# moth_v3_54mm_breakout.net
KiCad netlist of a schematic drawn in EAGLE
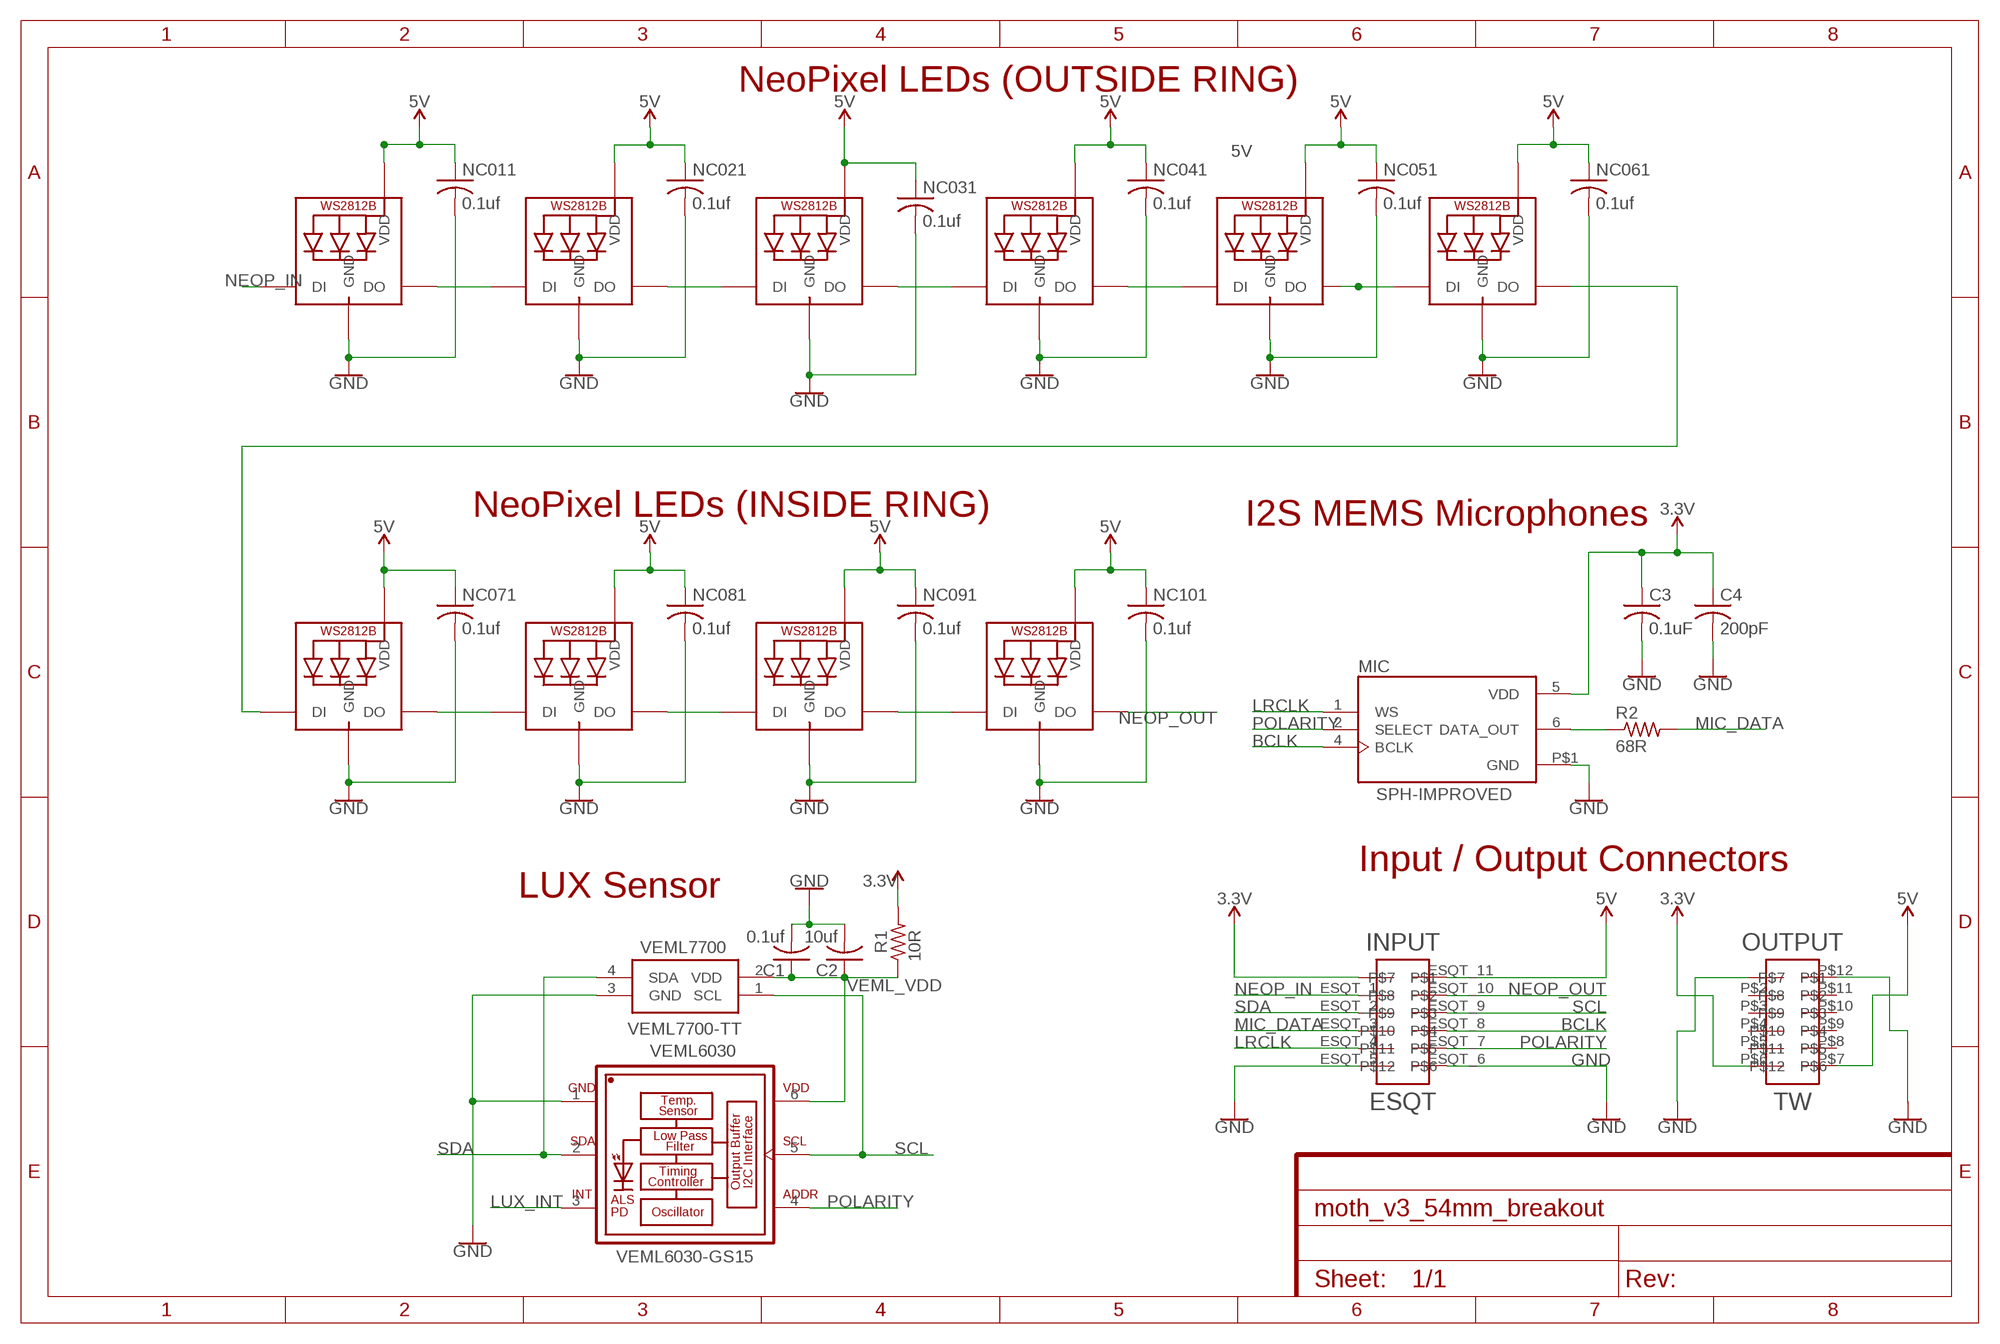
[diagram p0: schematic, sheet 1]

(export (version "E")
  (design (tool "Eeschema 10.0.6"))
  (components
    (comp (ref "C1")
      (value "0.1uf")
      (footprint "eagle-import:C0805")
      (libsource (lib "eagle-import") (part "C-USC0805"))
    )
    (comp (ref "C2")
      (value "10uf")
      (footprint "eagle-import:C0805")
      (libsource (lib "eagle-import") (part "C-USC0805"))
    )
    (comp (ref "C3")
      (value "0.1uF")
      (footprint "eagle-import:C0805")
      (libsource (lib "eagle-import") (part "C-USC0805"))
    )
    (comp (ref "C4")
      (value "200pF")
      (footprint "eagle-import:C0805")
      (libsource (lib "eagle-import") (part "C-USC0805"))
    )
    (comp (ref "INPUT")
      (value "ESQT")
      (footprint "eagle-import:SAMTEC_ESQT_2X6_THROUGH_HOLE")
      (libsource (lib "eagle-import") (part "SAMTEC_ESQT_2X6_THROUGH_HOLE"))
    )
    (comp (ref "MIC")
      (value "SPH-IMPROVED")
      (footprint "eagle-import:MIC_SPH0645LM4H-B_LARGER_RING")
      (libsource (lib "eagle-import") (part "SPH-IMPROVED"))
    )
    (comp (ref "NC011")
      (value "0.1uf")
      (footprint "eagle-import:C0805K")
      (libsource (lib "eagle-import") (part "C-USC0805K"))
    )
    (comp (ref "NC021")
      (value "0.1uf")
      (footprint "eagle-import:C0805K")
      (libsource (lib "eagle-import") (part "C-USC0805K"))
    )
    (comp (ref "NC031")
      (value "0.1uf")
      (footprint "eagle-import:C0805K")
      (libsource (lib "eagle-import") (part "C-USC0805K"))
    )
    (comp (ref "NC041")
      (value "0.1uf")
      (footprint "eagle-import:C0805K")
      (libsource (lib "eagle-import") (part "C-USC0805K"))
    )
    (comp (ref "NC051")
      (value "0.1uf")
      (footprint "eagle-import:C0805K")
      (libsource (lib "eagle-import") (part "C-USC0805K"))
    )
    (comp (ref "NC061")
      (value "0.1uf")
      (footprint "eagle-import:C0805K")
      (libsource (lib "eagle-import") (part "C-USC0805K"))
    )
    (comp (ref "NC071")
      (value "0.1uf")
      (footprint "eagle-import:C0805K")
      (libsource (lib "eagle-import") (part "C-USC0805K"))
    )
    (comp (ref "NC081")
      (value "0.1uf")
      (footprint "eagle-import:C0805K")
      (libsource (lib "eagle-import") (part "C-USC0805K"))
    )
    (comp (ref "NC091")
      (value "0.1uf")
      (footprint "eagle-import:C0805K")
      (libsource (lib "eagle-import") (part "C-USC0805K"))
    )
    (comp (ref "NC101")
      (value "0.1uf")
      (footprint "eagle-import:C0805K")
      (libsource (lib "eagle-import") (part "C-USC0805K"))
    )
    (comp (ref "NEO1")
      (value "WS2812B5050")
      (footprint "eagle-import:WS2812B")
      (libsource (lib "eagle-import") (part "WS2812B5050"))
    )
    (comp (ref "NEO2")
      (value "WS2812B5050")
      (footprint "eagle-import:WS2812B")
      (libsource (lib "eagle-import") (part "WS2812B5050"))
    )
    (comp (ref "NEO3")
      (value "WS2812B5050")
      (footprint "eagle-import:WS2812B")
      (libsource (lib "eagle-import") (part "WS2812B5050"))
    )
    (comp (ref "NEO4")
      (value "WS2812B5050")
      (footprint "eagle-import:WS2812B")
      (libsource (lib "eagle-import") (part "WS2812B5050"))
    )
    (comp (ref "NEO5")
      (value "WS2812B5050")
      (footprint "eagle-import:WS2812B")
      (libsource (lib "eagle-import") (part "WS2812B5050"))
    )
    (comp (ref "NEO6")
      (value "WS2812B5050")
      (footprint "eagle-import:WS2812B")
      (libsource (lib "eagle-import") (part "WS2812B5050"))
    )
    (comp (ref "NEO07")
      (value "WS2812B5050")
      (footprint "eagle-import:WS2812B")
      (libsource (lib "eagle-import") (part "WS2812B5050"))
    )
    (comp (ref "NEO08")
      (value "WS2812B5050")
      (footprint "eagle-import:WS2812B")
      (libsource (lib "eagle-import") (part "WS2812B5050"))
    )
    (comp (ref "NEO9")
      (value "WS2812B5050")
      (footprint "eagle-import:WS2812B")
      (libsource (lib "eagle-import") (part "WS2812B5050"))
    )
    (comp (ref "NEO10")
      (value "WS2812B5050")
      (footprint "eagle-import:WS2812B")
      (libsource (lib "eagle-import") (part "WS2812B5050"))
    )
    (comp (ref "OUTPUT")
      (value "TW")
      (footprint "eagle-import:SAMTEC_TW_2X6")
      (libsource (lib "eagle-import") (part "SAMTEC_TW_2X6_WITH_STABLE"))
    )
    (comp (ref "R1")
      (value "10R")
      (footprint "eagle-import:R0805")
      (libsource (lib "eagle-import") (part "audio amplifier example_970892_R-US_R0805"))
    )
    (comp (ref "R2")
      (value "68R")
      (footprint "eagle-import:M0805")
      (libsource (lib "eagle-import") (part "R-US_M0805"))
    )
    (comp (ref "VEML6030")
      (value "VEML6030-GS15")
      (footprint "eagle-import:VISHAY_VEML6030_2X2X0.87")
      (fields (field (name "MF") "Vishay Semiconductor"))
      (libsource (lib "eagle-import") (part "VEML6030-GS15"))
    )
    (comp (ref "VEML7700")
      (value "VEML7700-TT")
      (footprint "eagle-import:VEML7700")
      (fields (field (name "MOUSER_PART_NUMBER") "78-VEML7700-TT") (field (name "RS_PART_NUMBER") "1226791P"))
      (libsource (lib "eagle-import") (part "VEML7700-TT"))
    )
  )
  (nets
    (net (code "1") (name "/BCLK") (class "Default")
      (node (ref "INPUT") (pin "ESQT_8") (pinfunction "P$10_ESQT_8") (pintype "bidirectional"))
      (node (ref "MIC") (pin "4") (pinfunction "BCLK_4") (pintype "input"))
    )
    (net (code "2") (name "/LRCLK") (class "Default")
      (node (ref "INPUT") (pin "ESQT_4") (pinfunction "P$5_ESQT_4") (pintype "bidirectional"))
      (node (ref "MIC") (pin "1") (pinfunction "WS_1") (pintype "input"))
    )
    (net (code "3") (name "/LUX_INT") (class "Default")
      (node (ref "VEML6030") (pin "3") (pinfunction "INT_3") (pintype "output"))
    )
    (net (code "4") (name "/MIC_DATA") (class "Default")
      (node (ref "INPUT") (pin "ESQT_3") (pinfunction "P$4_ESQT_3") (pintype "bidirectional"))
      (node (ref "R2") (pin "2") (pinfunction "2_2") (pintype "passive"))
    )
    (net (code "5") (name "/NEOP_IN") (class "Default")
      (node (ref "INPUT") (pin "ESQT_1") (pinfunction "P$2_ESQT_1") (pintype "bidirectional"))
      (node (ref "NEO1") (pin "4-DIN") (pinfunction "DI_4-DIN") (pintype "input"))
    )
    (net (code "6") (name "/NEOP_OUT") (class "Default")
      (node (ref "INPUT") (pin "ESQT_10") (pinfunction "P$8_ESQT_10") (pintype "bidirectional"))
      (node (ref "NEO10") (pin "2-DOUT") (pinfunction "DO_2-DOUT") (pintype "output"))
    )
    (net (code "7") (name "/POLARITY") (class "Default")
      (node (ref "INPUT") (pin "ESQT_7") (pinfunction "P$11_ESQT_7") (pintype "bidirectional"))
      (node (ref "MIC") (pin "2") (pinfunction "SELECT_2") (pintype "input"))
      (node (ref "VEML6030") (pin "4") (pinfunction "ADDR_4") (pintype "bidirectional"))
    )
    (net (code "8") (name "/SCL") (class "Default")
      (node (ref "INPUT") (pin "ESQT_9") (pinfunction "P$9_ESQT_9") (pintype "bidirectional"))
      (node (ref "VEML6030") (pin "5") (pinfunction "SCL_5") (pintype "input"))
      (node (ref "VEML7700") (pin "1") (pinfunction "SCL_1") (pintype "bidirectional"))
    )
    (net (code "9") (name "/SDA") (class "Default")
      (node (ref "INPUT") (pin "ESQT_2") (pinfunction "P$3_ESQT_2") (pintype "bidirectional"))
      (node (ref "VEML6030") (pin "2") (pinfunction "SDA_2") (pintype "bidirectional"))
      (node (ref "VEML7700") (pin "4") (pinfunction "SDA_4") (pintype "bidirectional"))
    )
    (net (code "10") (name "/VEML_VDD") (class "Default")
      (node (ref "C1") (pin "1") (pinfunction "1_1") (pintype "passive"))
      (node (ref "C2") (pin "1") (pinfunction "1_1") (pintype "passive"))
      (node (ref "R1") (pin "1") (pinfunction "1_1") (pintype "passive"))
      (node (ref "VEML6030") (pin "6") (pinfunction "VDD_6") (pintype "power_in"))
      (node (ref "VEML7700") (pin "2") (pinfunction "VDD_2") (pintype "bidirectional"))
    )
    (net (code "11") (name "3.3V") (class "Default")
      (node (ref "C3") (pin "1") (pinfunction "1_1") (pintype "passive"))
      (node (ref "C4") (pin "1") (pinfunction "1_1") (pintype "passive"))
      (node (ref "INPUT") (pin "ESQT_0") (pinfunction "P$1_ESQT_0") (pintype "bidirectional"))
      (node (ref "MIC") (pin "5") (pinfunction "VDD_5") (pintype "power_in"))
      (node (ref "OUTPUT") (pin "P$6") (pinfunction "P$6_P$6") (pintype "bidirectional"))
      (node (ref "R1") (pin "2") (pinfunction "2_2") (pintype "passive"))
    )
    (net (code "12") (name "5V") (class "Default")
      (node (ref "INPUT") (pin "ESQT_11") (pinfunction "P$7_ESQT_11") (pintype "bidirectional"))
      (node (ref "NC011") (pin "1") (pinfunction "1_1") (pintype "passive"))
      (node (ref "NC021") (pin "1") (pinfunction "1_1") (pintype "passive"))
      (node (ref "NC031") (pin "1") (pinfunction "1_1") (pintype "passive"))
      (node (ref "NC041") (pin "1") (pinfunction "1_1") (pintype "passive"))
      (node (ref "NC051") (pin "1") (pinfunction "1_1") (pintype "passive"))
      (node (ref "NC061") (pin "1") (pinfunction "1_1") (pintype "passive"))
      (node (ref "NC071") (pin "1") (pinfunction "1_1") (pintype "passive"))
      (node (ref "NC081") (pin "1") (pinfunction "1_1") (pintype "passive"))
      (node (ref "NC091") (pin "1") (pinfunction "1_1") (pintype "passive"))
      (node (ref "NC101") (pin "1") (pinfunction "1_1") (pintype "passive"))
      (node (ref "NEO07") (pin "1-VDD") (pinfunction "VDD_1-VDD") (pintype "power_in"))
      (node (ref "NEO08") (pin "1-VDD") (pinfunction "VDD_1-VDD") (pintype "power_in"))
      (node (ref "NEO1") (pin "1-VDD") (pinfunction "VDD_1-VDD") (pintype "power_in"))
      (node (ref "NEO10") (pin "1-VDD") (pinfunction "VDD_1-VDD") (pintype "power_in"))
      (node (ref "NEO2") (pin "1-VDD") (pinfunction "VDD_1-VDD") (pintype "power_in"))
      (node (ref "NEO3") (pin "1-VDD") (pinfunction "VDD_1-VDD") (pintype "power_in"))
      (node (ref "NEO4") (pin "1-VDD") (pinfunction "VDD_1-VDD") (pintype "power_in"))
      (node (ref "NEO5") (pin "1-VDD") (pinfunction "VDD_1-VDD") (pintype "power_in"))
      (node (ref "NEO6") (pin "1-VDD") (pinfunction "VDD_1-VDD") (pintype "power_in"))
      (node (ref "NEO9") (pin "1-VDD") (pinfunction "VDD_1-VDD") (pintype "power_in"))
      (node (ref "OUTPUT") (pin "P$7") (pinfunction "P$12_P$7") (pintype "bidirectional"))
    )
    (net (code "13") (name "GND") (class "Default")
      (node (ref "C1") (pin "2") (pinfunction "2_2") (pintype "passive"))
      (node (ref "C2") (pin "2") (pinfunction "2_2") (pintype "passive"))
      (node (ref "C3") (pin "2") (pinfunction "2_2") (pintype "passive"))
      (node (ref "C4") (pin "2") (pinfunction "2_2") (pintype "passive"))
      (node (ref "INPUT") (pin "ESQT_5") (pinfunction "P$6_ESQT_5") (pintype "bidirectional"))
      (node (ref "INPUT") (pin "ESQT_6") (pinfunction "P$12_ESQT_6") (pintype "bidirectional"))
      (node (ref "MIC") (pin "P$1") (pinfunction "GND_P$1") (pintype "power_in"))
      (node (ref "NC011") (pin "2") (pinfunction "2_2") (pintype "passive"))
      (node (ref "NC021") (pin "2") (pinfunction "2_2") (pintype "passive"))
      (node (ref "NC031") (pin "2") (pinfunction "2_2") (pintype "passive"))
      (node (ref "NC041") (pin "2") (pinfunction "2_2") (pintype "passive"))
      (node (ref "NC051") (pin "2") (pinfunction "2_2") (pintype "passive"))
      (node (ref "NC061") (pin "2") (pinfunction "2_2") (pintype "passive"))
      (node (ref "NC071") (pin "2") (pinfunction "2_2") (pintype "passive"))
      (node (ref "NC081") (pin "2") (pinfunction "2_2") (pintype "passive"))
      (node (ref "NC091") (pin "2") (pinfunction "2_2") (pintype "passive"))
      (node (ref "NC101") (pin "2") (pinfunction "2_2") (pintype "passive"))
      (node (ref "NEO07") (pin "3-GND") (pinfunction "GND_3-GND") (pintype "power_in"))
      (node (ref "NEO08") (pin "3-GND") (pinfunction "GND_3-GND") (pintype "power_in"))
      (node (ref "NEO1") (pin "3-GND") (pinfunction "GND_3-GND") (pintype "power_in"))
      (node (ref "NEO10") (pin "3-GND") (pinfunction "GND_3-GND") (pintype "power_in"))
      (node (ref "NEO2") (pin "3-GND") (pinfunction "GND_3-GND") (pintype "power_in"))
      (node (ref "NEO3") (pin "3-GND") (pinfunction "GND_3-GND") (pintype "power_in"))
      (node (ref "NEO4") (pin "3-GND") (pinfunction "GND_3-GND") (pintype "power_in"))
      (node (ref "NEO5") (pin "3-GND") (pinfunction "GND_3-GND") (pintype "power_in"))
      (node (ref "NEO6") (pin "3-GND") (pinfunction "GND_3-GND") (pintype "power_in"))
      (node (ref "NEO9") (pin "3-GND") (pinfunction "GND_3-GND") (pintype "power_in"))
      (node (ref "OUTPUT") (pin "P$1") (pinfunction "P$1_P$1") (pintype "bidirectional"))
      (node (ref "OUTPUT") (pin "P$12") (pinfunction "P$7_P$12") (pintype "bidirectional"))
      (node (ref "VEML6030") (pin "1") (pinfunction "GND_1") (pintype "power_in"))
      (node (ref "VEML7700") (pin "3") (pinfunction "GND_3") (pintype "bidirectional"))
    )
    (net (code "14") (name "Net-(MIC-DATA_OUT)") (class "Default")
      (node (ref "MIC") (pin "6") (pinfunction "DATA_OUT_6") (pintype "output"))
      (node (ref "R2") (pin "1") (pinfunction "1_1") (pintype "passive"))
    )
    (net (code "15") (name "Net-(NEO1-DO)") (class "Default")
      (node (ref "NEO1") (pin "2-DOUT") (pinfunction "DO_2-DOUT") (pintype "output"))
      (node (ref "NEO2") (pin "4-DIN") (pinfunction "DI_4-DIN") (pintype "input"))
    )
    (net (code "16") (name "Net-(NEO2-DO)") (class "Default")
      (node (ref "NEO2") (pin "2-DOUT") (pinfunction "DO_2-DOUT") (pintype "output"))
      (node (ref "NEO3") (pin "4-DIN") (pinfunction "DI_4-DIN") (pintype "input"))
    )
    (net (code "17") (name "Net-(NEO3-DO)") (class "Default")
      (node (ref "NEO3") (pin "2-DOUT") (pinfunction "DO_2-DOUT") (pintype "output"))
      (node (ref "NEO4") (pin "4-DIN") (pinfunction "DI_4-DIN") (pintype "input"))
    )
    (net (code "18") (name "Net-(NEO4-DO)") (class "Default")
      (node (ref "NEO4") (pin "2-DOUT") (pinfunction "DO_2-DOUT") (pintype "output"))
      (node (ref "NEO5") (pin "4-DIN") (pinfunction "DI_4-DIN") (pintype "input"))
    )
    (net (code "19") (name "Net-(NEO5-DO)") (class "Default")
      (node (ref "NEO5") (pin "2-DOUT") (pinfunction "DO_2-DOUT") (pintype "output"))
      (node (ref "NEO6") (pin "4-DIN") (pinfunction "DI_4-DIN") (pintype "input"))
    )
    (net (code "20") (name "Net-(NEO07-DI)") (class "Default")
      (node (ref "NEO07") (pin "4-DIN") (pinfunction "DI_4-DIN") (pintype "input"))
      (node (ref "NEO6") (pin "2-DOUT") (pinfunction "DO_2-DOUT") (pintype "output"))
    )
    (net (code "21") (name "Net-(NEO07-DO)") (class "Default")
      (node (ref "NEO07") (pin "2-DOUT") (pinfunction "DO_2-DOUT") (pintype "output"))
      (node (ref "NEO08") (pin "4-DIN") (pinfunction "DI_4-DIN") (pintype "input"))
    )
    (net (code "22") (name "Net-(NEO08-DO)") (class "Default")
      (node (ref "NEO08") (pin "2-DOUT") (pinfunction "DO_2-DOUT") (pintype "output"))
      (node (ref "NEO9") (pin "4-DIN") (pinfunction "DI_4-DIN") (pintype "input"))
    )
    (net (code "23") (name "Net-(NEO10-DI)") (class "Default")
      (node (ref "NEO10") (pin "4-DIN") (pinfunction "DI_4-DIN") (pintype "input"))
      (node (ref "NEO9") (pin "2-DOUT") (pinfunction "DO_2-DOUT") (pintype "output"))
    )
    (net (code "24") (name "unconnected-(OUTPUT-P$8-PadP$11)") (class "Default")
      (node (ref "OUTPUT") (pin "P$11") (pinfunction "P$8_P$11") (pintype "bidirectional"))
    )
    (net (code "25") (name "unconnected-(OUTPUT-P$9-PadP$10)") (class "Default")
      (node (ref "OUTPUT") (pin "P$10") (pinfunction "P$9_P$10") (pintype "bidirectional"))
    )
    (net (code "26") (name "unconnected-(OUTPUT-P$10-PadP$9)") (class "Default")
      (node (ref "OUTPUT") (pin "P$9") (pinfunction "P$10_P$9") (pintype "bidirectional"))
    )
    (net (code "27") (name "unconnected-(OUTPUT-P$11-PadP$8)") (class "Default")
      (node (ref "OUTPUT") (pin "P$8") (pinfunction "P$11_P$8") (pintype "bidirectional"))
    )
    (net (code "28") (name "unconnected-(OUTPUT-PadP$2)") (class "Default")
      (node (ref "OUTPUT") (pin "P$2") (pinfunction "P$2_P$2") (pintype "bidirectional"))
    )
    (net (code "29") (name "unconnected-(OUTPUT-PadP$3)") (class "Default")
      (node (ref "OUTPUT") (pin "P$3") (pinfunction "P$3_P$3") (pintype "bidirectional"))
    )
    (net (code "30") (name "unconnected-(OUTPUT-PadP$4)") (class "Default")
      (node (ref "OUTPUT") (pin "P$4") (pinfunction "P$4_P$4") (pintype "bidirectional"))
    )
    (net (code "31") (name "unconnected-(OUTPUT-PadP$5)") (class "Default")
      (node (ref "OUTPUT") (pin "P$5") (pinfunction "P$5_P$5") (pintype "bidirectional"))
    )
  )
)
